# final.net
KiCad netlist of a schematic drawn in EAGLE
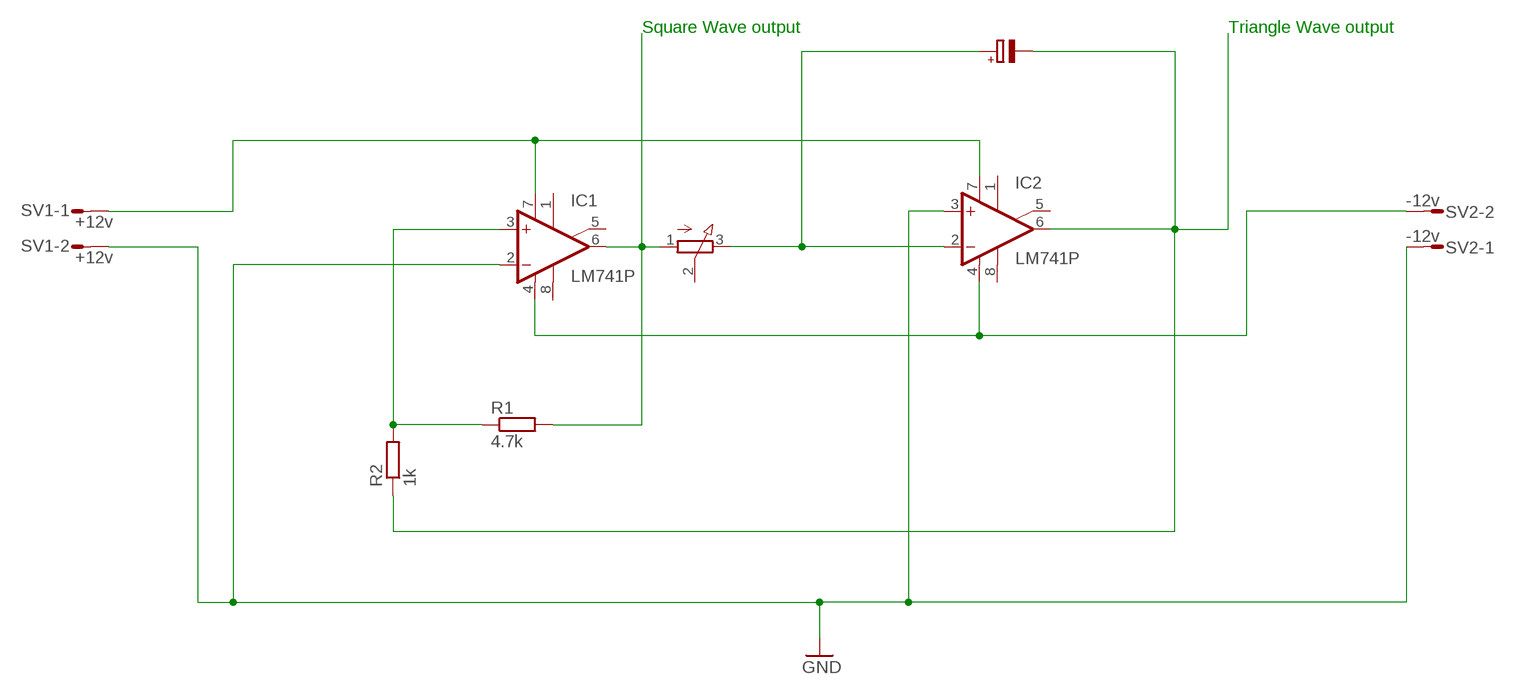
[diagram p0: schematic, sheet 1]

(export (version "E")
  (design (tool "Eeschema 10.0.6"))
  (components
    (comp (ref "C1")
      (value "0.1u")
      (footprint "eagle-import:E5-6")
      (libsource (lib "eagle-import") (part "CPOL-EUE5-6"))
    )
    (comp (ref "IC1")
      (value "LM741P")
      (footprint "eagle-import:DIL08")
      (libsource (lib "eagle-import") (part "741PLM"))
    )
    (comp (ref "IC2")
      (value "LM741P")
      (footprint "eagle-import:DIL08")
      (libsource (lib "eagle-import") (part "741PLM"))
    )
    (comp (ref "P1")
      (value "4.7k--47k")
      (footprint "eagle-import:3RP_1610N")
      (libsource (lib "eagle-import") (part "3RP/1610N"))
    )
    (comp (ref "R1")
      (value "4.7k")
      (footprint "eagle-import:P0613_15")
      (libsource (lib "eagle-import") (part "R-EU_0613/15"))
    )
    (comp (ref "R2")
      (value "1k")
      (footprint "eagle-import:P0613_15")
      (libsource (lib "eagle-import") (part "R-EU_0613/15"))
    )
    (comp (ref "SV1")
      (value "+12v")
      (footprint "eagle-import:L02P")
      (libsource (lib "eagle-import") (part "L02P"))
    )
    (comp (ref "SV2")
      (value "-12v")
      (footprint "eagle-import:L02P")
      (libsource (lib "eagle-import") (part "L02P"))
    )
  )
  (nets
    (net (code "1") (name "GND") (class "Default")
      (node (ref "IC1") (pin "2") (pinfunction "-IN_2") (pintype "input"))
      (node (ref "IC2") (pin "3") (pinfunction "+IN_3") (pintype "input"))
      (node (ref "SV1") (pin "2") (pinfunction "S_2") (pintype "passive"))
      (node (ref "SV2") (pin "1") (pinfunction "S_1") (pintype "passive"))
    )
    (net (code "2") (name "Net-(IC1-+IN)") (class "Default")
      (node (ref "IC1") (pin "3") (pinfunction "+IN_3") (pintype "input"))
      (node (ref "R1") (pin "1") (pinfunction "1_1") (pintype "passive"))
      (node (ref "R2") (pin "2") (pinfunction "2_2") (pintype "passive"))
    )
    (net (code "3") (name "Net-(IC1-OUT)") (class "Default")
      (node (ref "IC1") (pin "6") (pinfunction "OUT_6") (pintype "output"))
      (node (ref "P1") (pin "1") (pinfunction "A_1") (pintype "passive"))
      (node (ref "R1") (pin "2") (pinfunction "2_2") (pintype "passive"))
    )
    (net (code "4") (name "Net-(IC1-V+)") (class "Default")
      (node (ref "IC1") (pin "7") (pinfunction "V+_7") (pintype "power_in"))
      (node (ref "IC2") (pin "7") (pinfunction "V+_7") (pintype "power_in"))
      (node (ref "SV1") (pin "1") (pinfunction "S_1") (pintype "passive"))
    )
    (net (code "5") (name "Net-(IC1-V-)") (class "Default")
      (node (ref "IC1") (pin "4") (pinfunction "V-_4") (pintype "power_in"))
      (node (ref "IC2") (pin "4") (pinfunction "V-_4") (pintype "power_in"))
      (node (ref "SV2") (pin "2") (pinfunction "S_2") (pintype "passive"))
    )
    (net (code "6") (name "Net-(IC2--IN)") (class "Default")
      (node (ref "C1") (pin "+") (pinfunction "+_+") (pintype "passive"))
      (node (ref "IC2") (pin "2") (pinfunction "-IN_2") (pintype "input"))
      (node (ref "P1") (pin "3") (pinfunction "E_3") (pintype "passive"))
    )
    (net (code "7") (name "Net-(IC2-OUT)") (class "Default")
      (node (ref "C1") (pin "-") (pinfunction "-_-") (pintype "passive"))
      (node (ref "IC2") (pin "6") (pinfunction "OUT_6") (pintype "output"))
      (node (ref "R2") (pin "1") (pinfunction "1_1") (pintype "passive"))
    )
    (net (code "8") (name "unconnected-(IC1-ON1-Pad1)") (class "Default")
      (node (ref "IC1") (pin "1") (pinfunction "ON1_1") (pintype "passive"))
    )
    (net (code "9") (name "unconnected-(IC1-ON2-Pad5)") (class "Default")
      (node (ref "IC1") (pin "5") (pinfunction "ON2_5") (pintype "passive"))
    )
    (net (code "10") (name "unconnected-(IC1-OPT-Pad8)") (class "Default")
      (node (ref "IC1") (pin "8") (pinfunction "OPT_8") (pintype "passive"))
    )
    (net (code "11") (name "unconnected-(IC2-ON1-Pad1)") (class "Default")
      (node (ref "IC2") (pin "1") (pinfunction "ON1_1") (pintype "passive"))
    )
    (net (code "12") (name "unconnected-(IC2-ON2-Pad5)") (class "Default")
      (node (ref "IC2") (pin "5") (pinfunction "ON2_5") (pintype "passive"))
    )
    (net (code "13") (name "unconnected-(IC2-OPT-Pad8)") (class "Default")
      (node (ref "IC2") (pin "8") (pinfunction "OPT_8") (pintype "passive"))
    )
    (net (code "14") (name "unconnected-(P1-S-Pad2)") (class "Default")
      (node (ref "P1") (pin "2") (pinfunction "S_2") (pintype "passive"))
    )
  )
)
